# Grove_-_PH_Sensor_v1_0.net
KiCad netlist of a schematic drawn in EAGLE
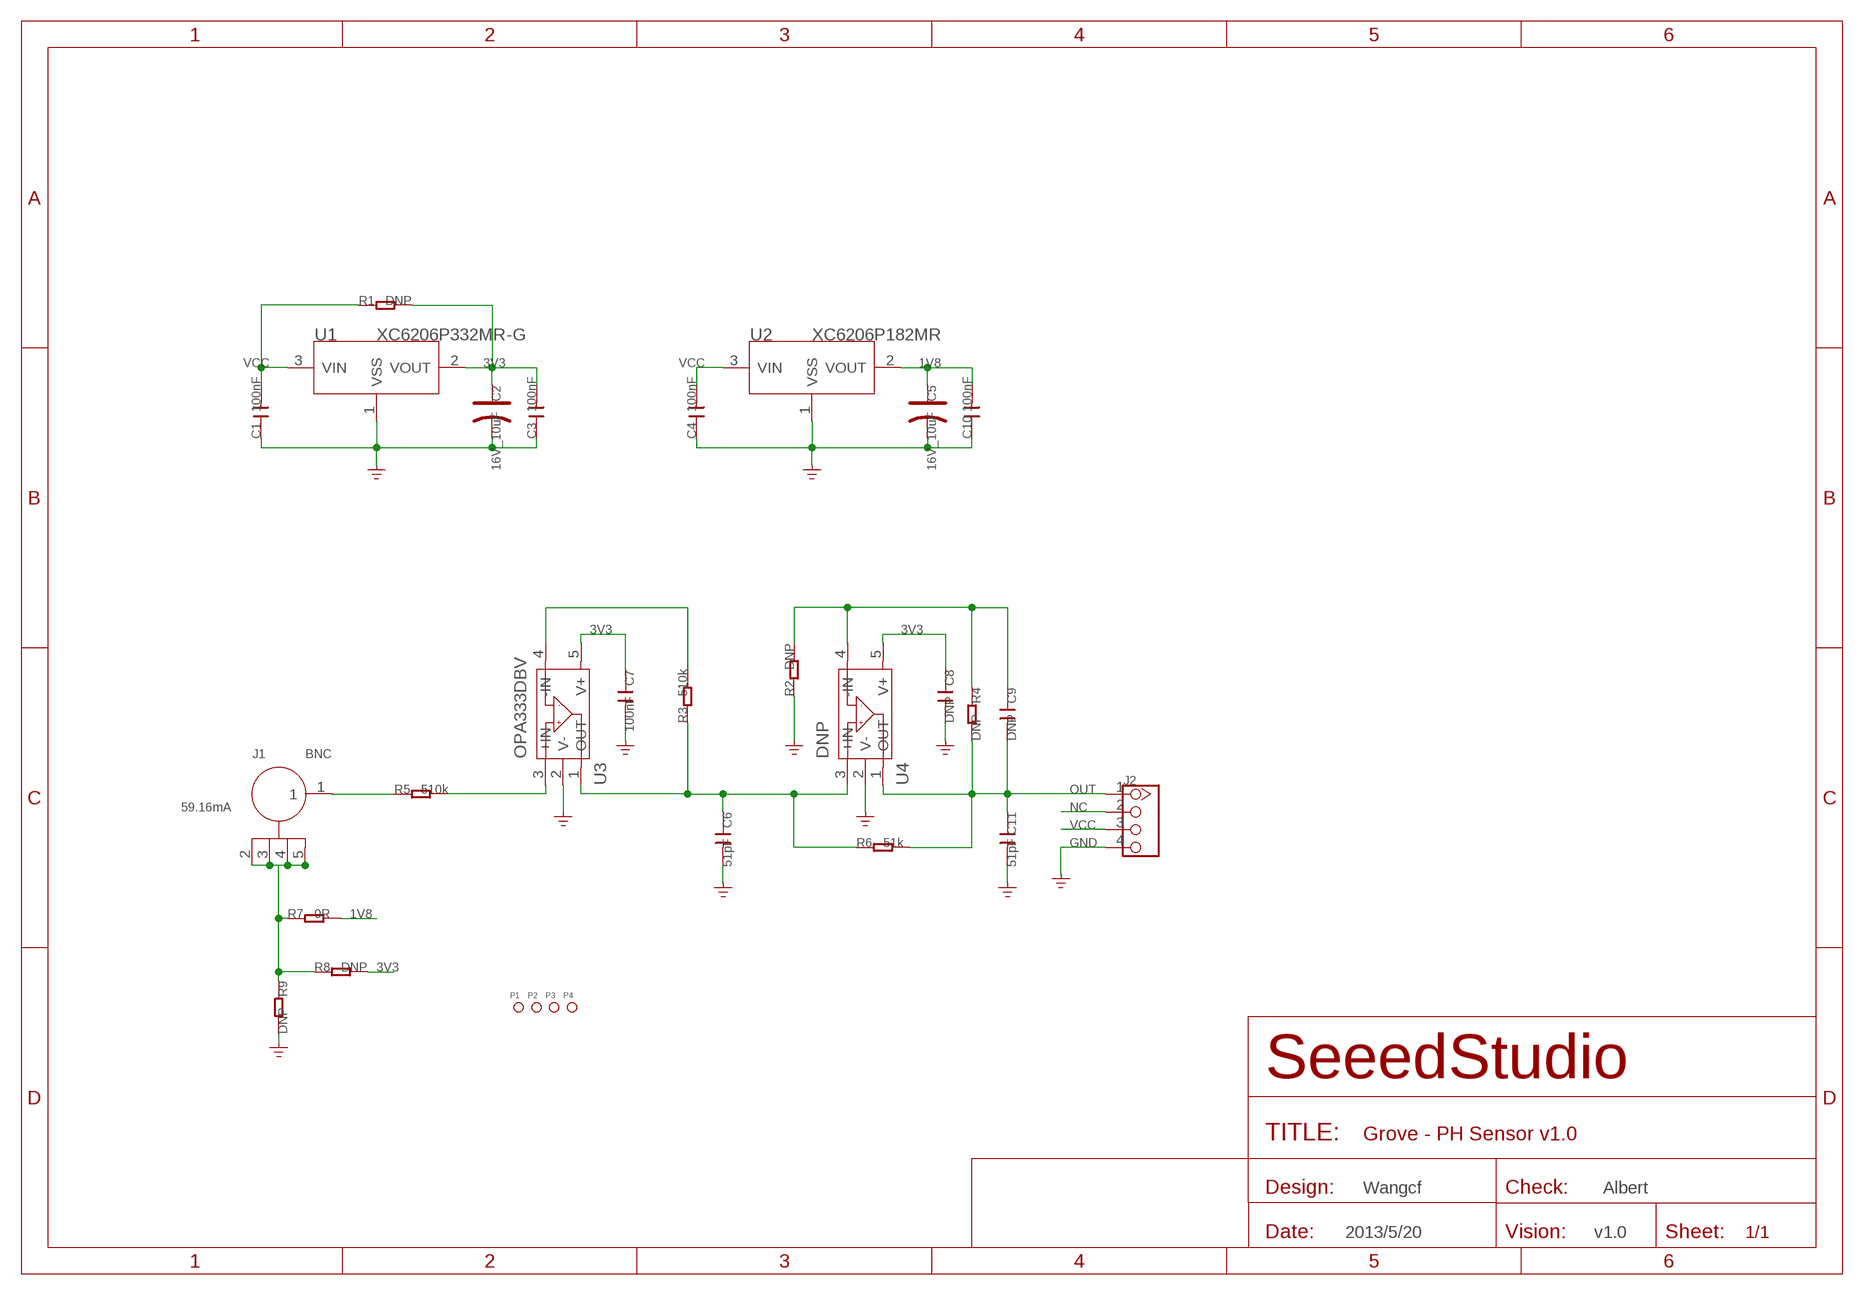
[diagram p0: schematic, sheet 1]

(export (version "E")
  (design (tool "Eeschema 10.0.6"))
  (components
    (comp (ref "C1")
      (value "100nF")
      (footprint "eagle-import:C0603")
      (libsource (lib "eagle-import") (part "C-0603"))
    )
    (comp (ref "C2")
      (value "16V_10uF")
      (footprint "eagle-import:AVX-A")
      (libsource (lib "eagle-import") (part "CAP-AVX-A"))
    )
    (comp (ref "C3")
      (value "100nF")
      (footprint "eagle-import:C0603")
      (libsource (lib "eagle-import") (part "C-0603"))
    )
    (comp (ref "C4")
      (value "100nF")
      (footprint "eagle-import:C0603")
      (libsource (lib "eagle-import") (part "C-0603"))
    )
    (comp (ref "C5")
      (value "16V_10uF")
      (footprint "eagle-import:AVX-A")
      (libsource (lib "eagle-import") (part "CAP-AVX-A"))
    )
    (comp (ref "C6")
      (value "51pF")
      (footprint "eagle-import:C0603")
      (libsource (lib "eagle-import") (part "C-0603"))
    )
    (comp (ref "C7")
      (value "100nF")
      (footprint "eagle-import:C0603")
      (libsource (lib "eagle-import") (part "C-0603"))
    )
    (comp (ref "C8")
      (value "DNP")
      (footprint "eagle-import:C0603")
      (libsource (lib "eagle-import") (part "C-0603"))
    )
    (comp (ref "C9")
      (value "DNP")
      (footprint "eagle-import:C0603")
      (libsource (lib "eagle-import") (part "C-0603"))
    )
    (comp (ref "C10")
      (value "100nF")
      (footprint "eagle-import:C0603")
      (libsource (lib "eagle-import") (part "C-0603"))
    )
    (comp (ref "C11")
      (value "51pF")
      (footprint "eagle-import:C0603")
      (libsource (lib "eagle-import") (part "C-0603"))
    )
    (comp (ref "J1")
      (value "BNC")
      (footprint "eagle-import:2P-10X10X12H-90D")
      (libsource (lib "eagle-import") (part "BNC'BNC-KYWE-1'"))
    )
    (comp (ref "J2")
      (value "TWIG-4P-2.0-2.0")
      (footprint "eagle-import:4P-2.0")
      (libsource (lib "eagle-import") (part "TWIG-4P-2.0-2.0"))
    )
    (comp (ref "P1")
      (value "PAD-MARK")
      (footprint "eagle-import:ROUND-MARK-1.0")
      (fields (field (name "PARTNO") "DNP"))
      (libsource (lib "eagle-import") (part "PAD-MARK"))
    )
    (comp (ref "P2")
      (value "PAD-MARK")
      (footprint "eagle-import:ROUND-MARK-1.0")
      (fields (field (name "PARTNO") "DNP"))
      (libsource (lib "eagle-import") (part "PAD-MARK"))
    )
    (comp (ref "P3")
      (value "PAD-MARK")
      (footprint "eagle-import:ROUND-MARK-1.0")
      (fields (field (name "PARTNO") "DNP"))
      (libsource (lib "eagle-import") (part "PAD-MARK"))
    )
    (comp (ref "P4")
      (value "PAD-MARK")
      (footprint "eagle-import:ROUND-MARK-1.0")
      (fields (field (name "PARTNO") "DNP"))
      (libsource (lib "eagle-import") (part "PAD-MARK"))
    )
    (comp (ref "R1")
      (value "DNP")
      (footprint "eagle-import:R0603")
      (libsource (lib "eagle-import") (part "R-0603"))
    )
    (comp (ref "R2")
      (value "DNP")
      (footprint "eagle-import:R0603")
      (libsource (lib "eagle-import") (part "R-0603"))
    )
    (comp (ref "R3")
      (value "510k")
      (footprint "eagle-import:R0603")
      (libsource (lib "eagle-import") (part "R-0603"))
    )
    (comp (ref "R4")
      (value "DNP")
      (footprint "eagle-import:R0603")
      (libsource (lib "eagle-import") (part "R-0603"))
    )
    (comp (ref "R5")
      (value "510k")
      (footprint "eagle-import:R0603")
      (libsource (lib "eagle-import") (part "R-0603"))
    )
    (comp (ref "R6")
      (value "51k")
      (footprint "eagle-import:R0603")
      (libsource (lib "eagle-import") (part "R-0603"))
    )
    (comp (ref "R7")
      (value "0R")
      (footprint "eagle-import:R0603")
      (libsource (lib "eagle-import") (part "R-0603"))
    )
    (comp (ref "R8")
      (value "DNP")
      (footprint "eagle-import:R0603")
      (libsource (lib "eagle-import") (part "R-0603"))
    )
    (comp (ref "R9")
      (value "DNP")
      (footprint "eagle-import:R0603")
      (libsource (lib "eagle-import") (part "R-0603"))
    )
    (comp (ref "U1")
      (value "XC6206P332MR-G")
      (footprint "eagle-import:SOT23")
      (libsource (lib "eagle-import") (part "XC6206MR"))
    )
    (comp (ref "U2")
      (value "XC6206P182MR")
      (footprint "eagle-import:SOT23")
      (libsource (lib "eagle-import") (part "XC6206MR"))
    )
    (comp (ref "U3")
      (value "OPA333DBV")
      (footprint "eagle-import:SOT23-5")
      (libsource (lib "eagle-import") (part "OPA333DBV"))
    )
    (comp (ref "U4")
      (value "DNP")
      (footprint "eagle-import:SOT23-5")
      (libsource (lib "eagle-import") (part "OPA333DBV"))
    )
  )
  (nets
    (net (code "1") (name "/1V8") (class "Default")
      (node (ref "C10") (pin "2") (pinfunction "2_2") (pintype "passive"))
      (node (ref "C5") (pin "+") (pinfunction "+_+") (pintype "passive"))
      (node (ref "R7") (pin "2") (pinfunction "2_2") (pintype "passive"))
      (node (ref "U2") (pin "2") (pinfunction "VOUT_2") (pintype "output"))
    )
    (net (code "2") (name "/3V3") (class "Default")
      (node (ref "C2") (pin "+") (pinfunction "+_+") (pintype "passive"))
      (node (ref "C3") (pin "2") (pinfunction "2_2") (pintype "passive"))
      (node (ref "C7") (pin "1") (pinfunction "1_1") (pintype "passive"))
      (node (ref "C8") (pin "1") (pinfunction "1_1") (pintype "passive"))
      (node (ref "R1") (pin "2") (pinfunction "2_2") (pintype "passive"))
      (node (ref "R8") (pin "2") (pinfunction "2_2") (pintype "passive"))
      (node (ref "U1") (pin "2") (pinfunction "VOUT_2") (pintype "output"))
      (node (ref "U3") (pin "5") (pinfunction "V+_5") (pintype "bidirectional"))
      (node (ref "U4") (pin "5") (pinfunction "V+_5") (pintype "bidirectional"))
    )
    (net (code "3") (name "/NC") (class "Default")
      (node (ref "J2") (pin "2") (pinfunction "2_2") (pintype "bidirectional"))
    )
    (net (code "4") (name "/OUT") (class "Default")
      (node (ref "C11") (pin "1") (pinfunction "1_1") (pintype "passive"))
      (node (ref "C9") (pin "2") (pinfunction "2_2") (pintype "passive"))
      (node (ref "J2") (pin "1") (pinfunction "1_1") (pintype "bidirectional"))
      (node (ref "R4") (pin "2") (pinfunction "2_2") (pintype "passive"))
      (node (ref "R6") (pin "2") (pinfunction "2_2") (pintype "passive"))
      (node (ref "U4") (pin "1") (pinfunction "OUT_1") (pintype "bidirectional"))
    )
    (net (code "5") (name "/VCC") (class "Default")
      (node (ref "C1") (pin "2") (pinfunction "2_2") (pintype "passive"))
      (node (ref "C4") (pin "2") (pinfunction "2_2") (pintype "passive"))
      (node (ref "J2") (pin "3") (pinfunction "3_3") (pintype "bidirectional"))
      (node (ref "R1") (pin "1") (pinfunction "1_1") (pintype "passive"))
      (node (ref "U1") (pin "3") (pinfunction "VIN_3") (pintype "input"))
      (node (ref "U2") (pin "3") (pinfunction "VIN_3") (pintype "input"))
    )
    (net (code "6") (name "GND_POWER") (class "Default")
      (node (ref "C1") (pin "1") (pinfunction "1_1") (pintype "passive"))
      (node (ref "C10") (pin "1") (pinfunction "1_1") (pintype "passive"))
      (node (ref "C11") (pin "2") (pinfunction "2_2") (pintype "passive"))
      (node (ref "C2") (pin "-") (pinfunction "-_-") (pintype "passive"))
      (node (ref "C3") (pin "1") (pinfunction "1_1") (pintype "passive"))
      (node (ref "C4") (pin "1") (pinfunction "1_1") (pintype "passive"))
      (node (ref "C5") (pin "-") (pinfunction "-_-") (pintype "passive"))
      (node (ref "C6") (pin "2") (pinfunction "2_2") (pintype "passive"))
      (node (ref "C7") (pin "2") (pinfunction "2_2") (pintype "passive"))
      (node (ref "C8") (pin "2") (pinfunction "2_2") (pintype "passive"))
      (node (ref "J2") (pin "4") (pinfunction "4_4") (pintype "bidirectional"))
      (node (ref "R2") (pin "1") (pinfunction "1_1") (pintype "passive"))
      (node (ref "R9") (pin "2") (pinfunction "2_2") (pintype "passive"))
      (node (ref "U1") (pin "1") (pinfunction "VSS_1") (pintype "power_in"))
      (node (ref "U2") (pin "1") (pinfunction "VSS_1") (pintype "power_in"))
      (node (ref "U3") (pin "2") (pinfunction "V-_2") (pintype "bidirectional"))
      (node (ref "U4") (pin "2") (pinfunction "V-_2") (pintype "bidirectional"))
    )
    (net (code "7") (name "Net-(J1-Pad1)") (class "Default")
      (node (ref "J1") (pin "1") (pinfunction "1_1") (pintype "bidirectional"))
      (node (ref "R5") (pin "1") (pinfunction "1_1") (pintype "passive"))
    )
    (net (code "8") (name "Net-(J1-Pad2)") (class "Default")
      (node (ref "J1") (pin "2") (pinfunction "2_2") (pintype "bidirectional"))
      (node (ref "J1") (pin "3") (pinfunction "3_3") (pintype "bidirectional"))
      (node (ref "J1") (pin "4") (pinfunction "4_4") (pintype "bidirectional"))
      (node (ref "J1") (pin "5") (pinfunction "5_5") (pintype "bidirectional"))
      (node (ref "R7") (pin "1") (pinfunction "1_1") (pintype "passive"))
      (node (ref "R8") (pin "1") (pinfunction "1_1") (pintype "passive"))
      (node (ref "R9") (pin "1") (pinfunction "1_1") (pintype "passive"))
    )
    (net (code "9") (name "Net-(U3-+IN)") (class "Default")
      (node (ref "R5") (pin "2") (pinfunction "2_2") (pintype "passive"))
      (node (ref "U3") (pin "3") (pinfunction "+IN_3") (pintype "bidirectional"))
    )
    (net (code "10") (name "Net-(U3--IN)") (class "Default")
      (node (ref "R3") (pin "2") (pinfunction "2_2") (pintype "passive"))
      (node (ref "U3") (pin "4") (pinfunction "-IN_4") (pintype "bidirectional"))
    )
    (net (code "11") (name "Net-(U3-OUT)") (class "Default")
      (node (ref "C6") (pin "1") (pinfunction "1_1") (pintype "passive"))
      (node (ref "R3") (pin "1") (pinfunction "1_1") (pintype "passive"))
      (node (ref "R6") (pin "1") (pinfunction "1_1") (pintype "passive"))
      (node (ref "U3") (pin "1") (pinfunction "OUT_1") (pintype "bidirectional"))
      (node (ref "U4") (pin "3") (pinfunction "+IN_3") (pintype "bidirectional"))
    )
    (net (code "12") (name "Net-(U4--IN)") (class "Default")
      (node (ref "C9") (pin "1") (pinfunction "1_1") (pintype "passive"))
      (node (ref "R2") (pin "2") (pinfunction "2_2") (pintype "passive"))
      (node (ref "R4") (pin "1") (pinfunction "1_1") (pintype "passive"))
      (node (ref "U4") (pin "4") (pinfunction "-IN_4") (pintype "bidirectional"))
    )
  )
)
